# frankfurt_eth_arm.net
KiCad netlist of a schematic drawn in EAGLE
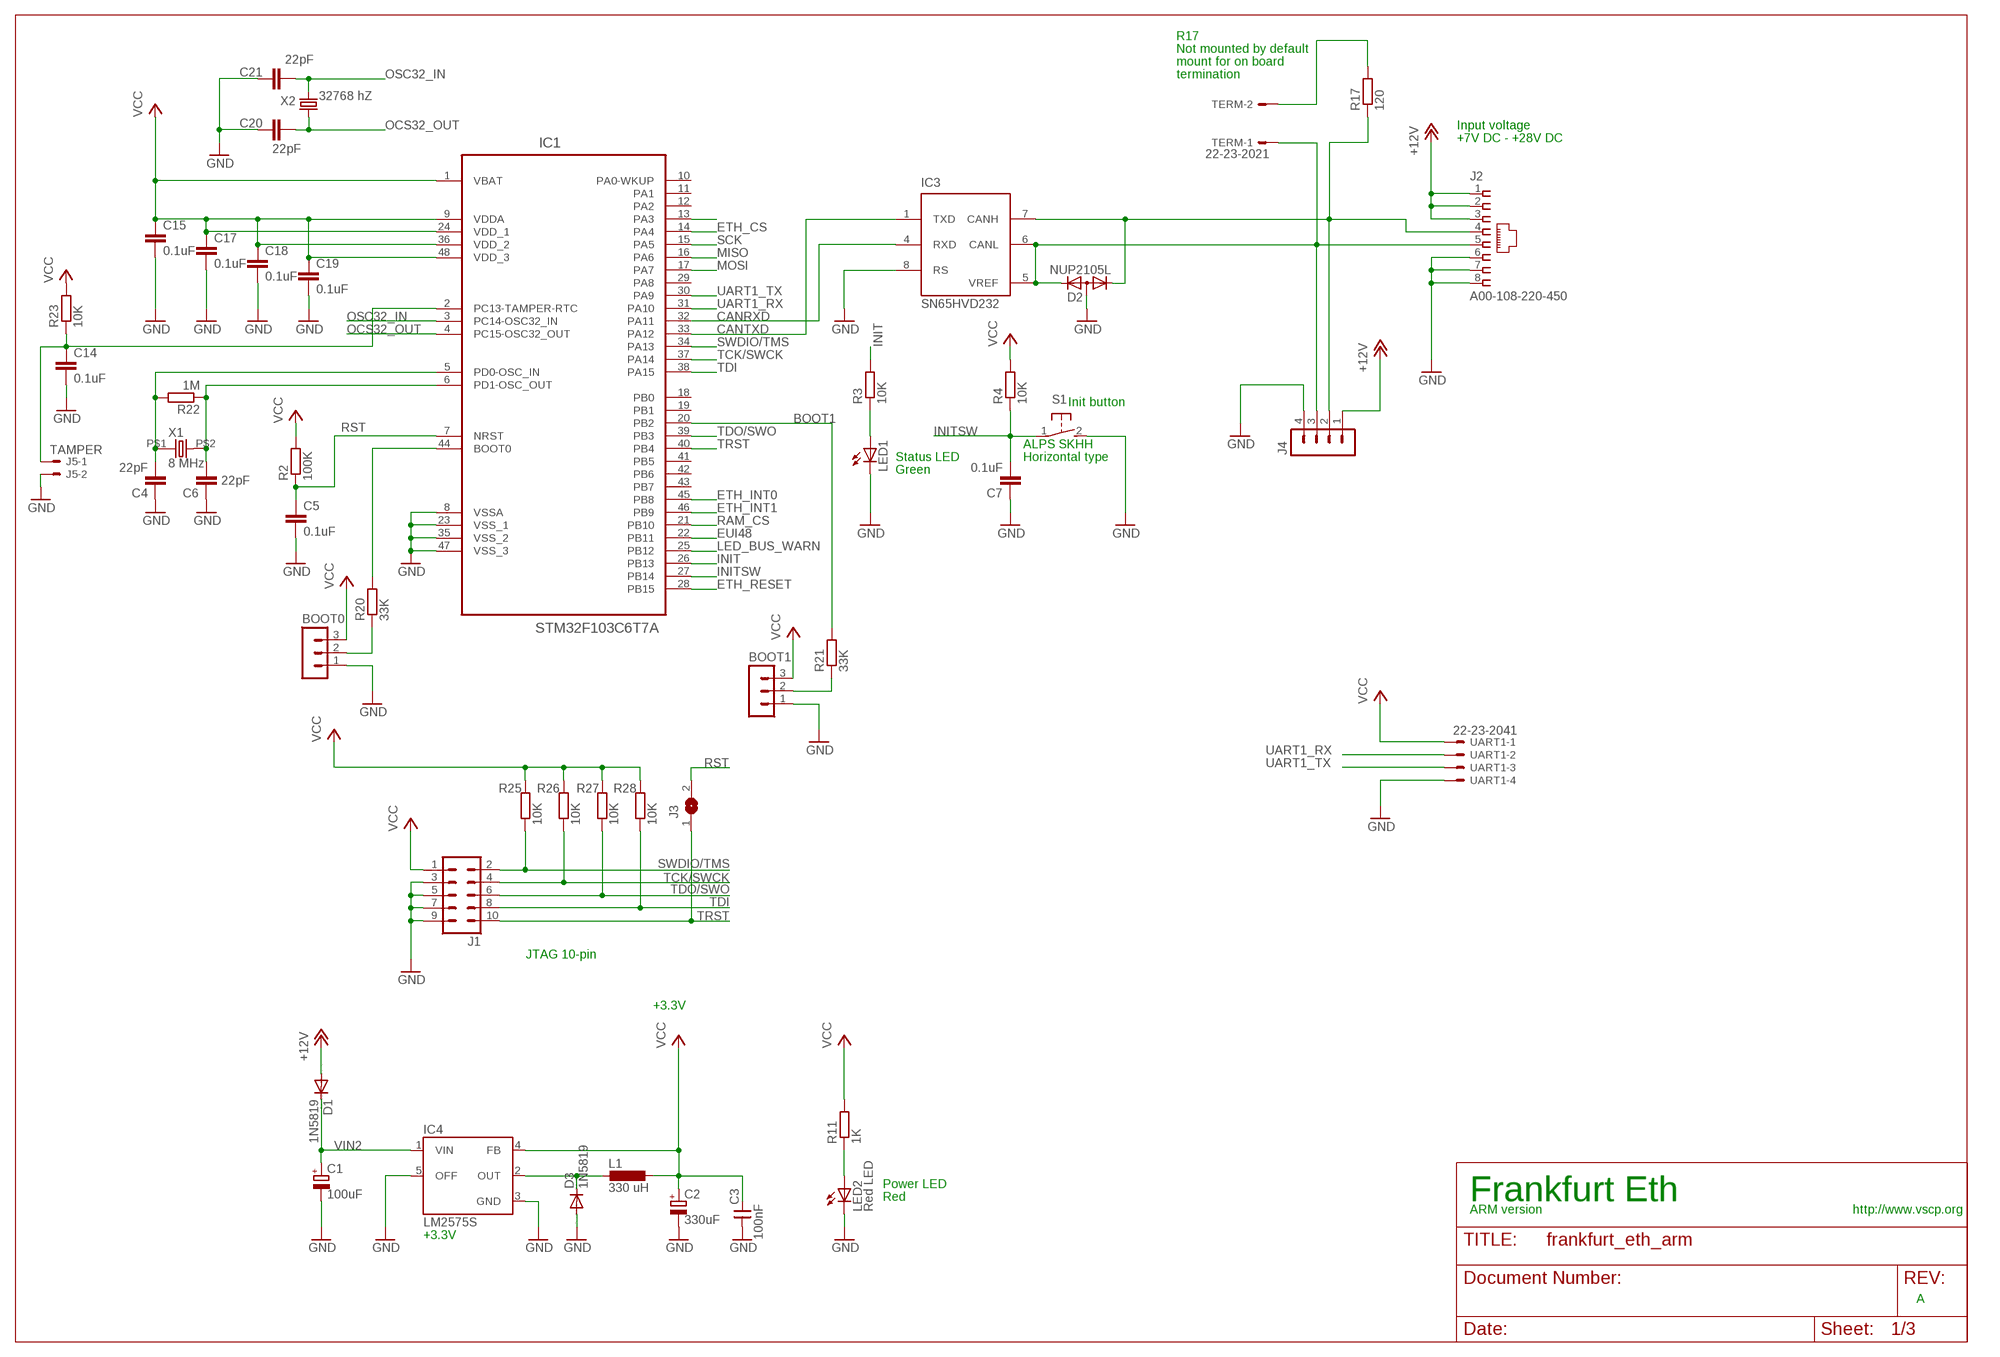
[diagram p0: schematic, sheet 1]
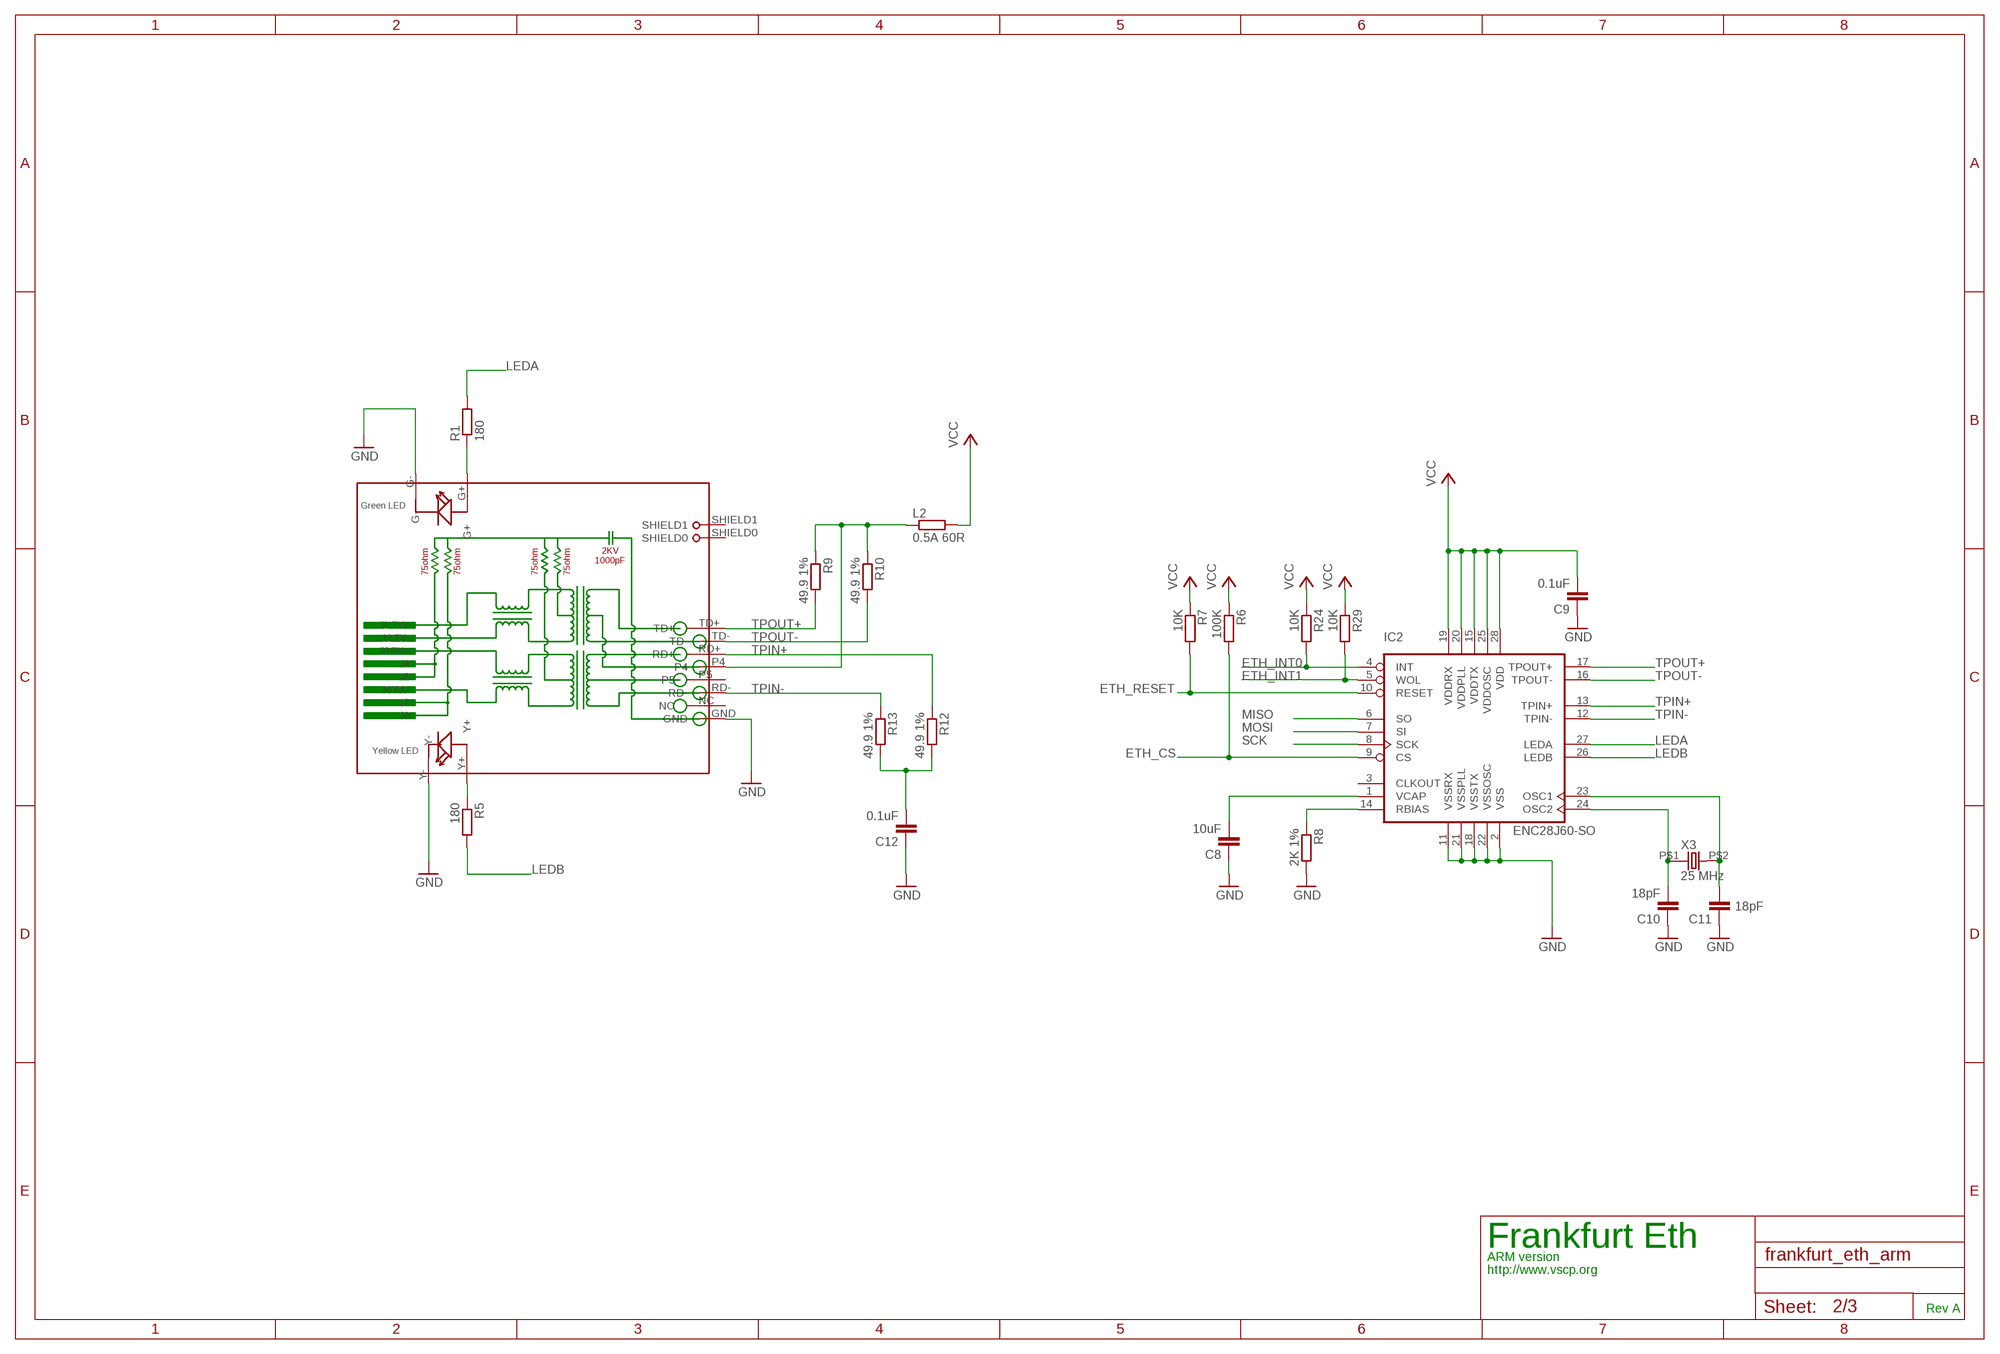
[diagram p1: schematic, sheet 2]
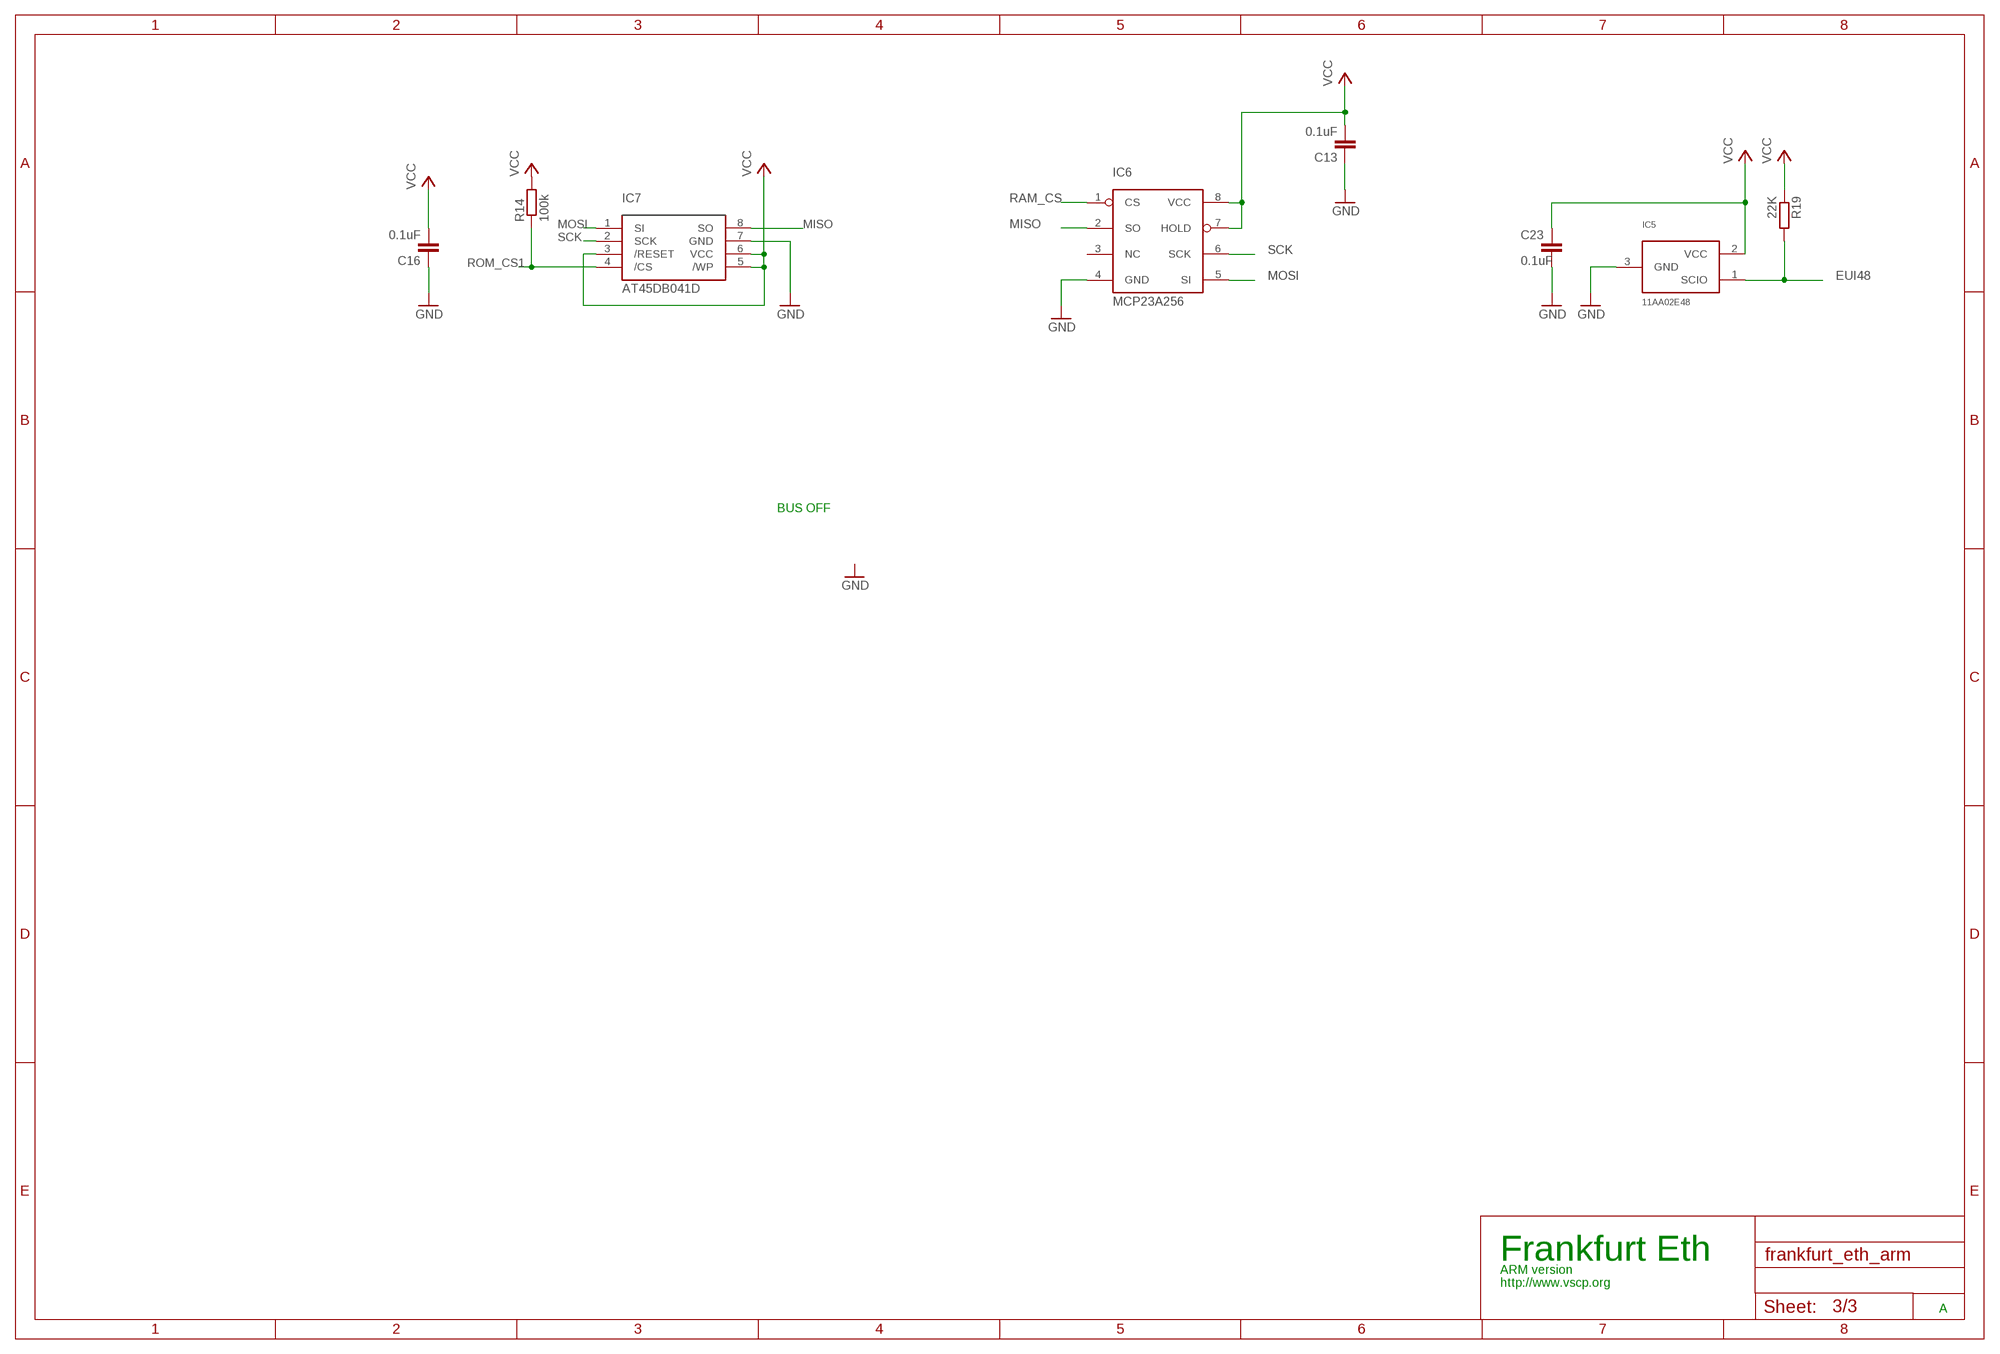
[diagram p2: schematic, sheet 3]

(export (version "E")
  (design (tool "Eeschema 10.0.6"))
  (components
    (comp (ref "BOOT0")
      (value "MA03-1")
      (footprint "eagle-import:MA03-1")
      (libsource (lib "eagle-import") (part "MA03-1"))
    )
    (comp (ref "BOOT1")
      (value "MA03-1")
      (footprint "eagle-import:MA03-1")
      (libsource (lib "eagle-import") (part "MA03-1"))
    )
    (comp (ref "C1")
      (value "100uF")
      (footprint "eagle-import:PANASONIC_D")
      (libsource (lib "eagle-import") (part "CPOL-EUD"))
    )
    (comp (ref "C2")
      (value "330uF")
      (footprint "eagle-import:PANASONIC_D")
      (libsource (lib "eagle-import") (part "CPOL-EUD"))
    )
    (comp (ref "C3")
      (value "100nF")
      (footprint "eagle-import:0805")
      (libsource (lib "eagle-import") (part "CNP-0805"))
    )
    (comp (ref "C4")
      (value "22pF")
      (footprint "eagle-import:C0805")
      (libsource (lib "eagle-import") (part "C-EUC0805"))
    )
    (comp (ref "C5")
      (value "0.1uF")
      (footprint "eagle-import:C0805")
      (libsource (lib "eagle-import") (part "C-EUC0805"))
    )
    (comp (ref "C6")
      (value "22pF")
      (footprint "eagle-import:C0805")
      (libsource (lib "eagle-import") (part "C-EUC0805"))
    )
    (comp (ref "C7")
      (value "0.1uF")
      (footprint "eagle-import:C0805")
      (libsource (lib "eagle-import") (part "C-EUC0805"))
    )
    (comp (ref "C14")
      (value "0.1uF")
      (footprint "eagle-import:C0805")
      (libsource (lib "eagle-import") (part "C-EUC0805"))
    )
    (comp (ref "C15")
      (value "0.1uF")
      (footprint "eagle-import:C0805")
      (libsource (lib "eagle-import") (part "C-EUC0805"))
    )
    (comp (ref "C17")
      (value "0.1uF")
      (footprint "eagle-import:C0805")
      (libsource (lib "eagle-import") (part "C-EUC0805"))
    )
    (comp (ref "C18")
      (value "0.1uF")
      (footprint "eagle-import:C0805")
      (libsource (lib "eagle-import") (part "C-EUC0805"))
    )
    (comp (ref "C19")
      (value "0.1uF")
      (footprint "eagle-import:C0805")
      (libsource (lib "eagle-import") (part "C-EUC0805"))
    )
    (comp (ref "C20")
      (value "22pF")
      (footprint "eagle-import:C0805")
      (libsource (lib "eagle-import") (part "C-EUC0805"))
    )
    (comp (ref "C21")
      (value "22pF")
      (footprint "eagle-import:C0805")
      (libsource (lib "eagle-import") (part "C-EUC0805"))
    )
    (comp (ref "D1")
      (value "1N5819")
      (footprint "eagle-import:SOD123")
      (libsource (lib "eagle-import") (part "DIODE-SOD123"))
    )
    (comp (ref "D2")
      (value "NUP2105L")
      (footprint "eagle-import:SOT23")
      (libsource (lib "eagle-import") (part "DIODE-2CA|ACSOT23"))
    )
    (comp (ref "D3")
      (value "1N5819")
      (footprint "eagle-import:SOD123")
      (libsource (lib "eagle-import") (part "DIODE-SOD123"))
    )
    (comp (ref "IC1")
      (value "STM32F103C6T7A")
      (footprint "eagle-import:QFP50P900X900X160-48N")
      (libsource (lib "eagle-import") (part "STM32F103C6T7A"))
    )
    (comp (ref "IC3")
      (value "SN65HVD232")
      (footprint "eagle-import:SO-08")
      (libsource (lib "eagle-import") (part "MCP2551SN"))
    )
    (comp (ref "IC4")
      (value "LM2575S")
      (footprint "eagle-import:TO263-5")
      (libsource (lib "eagle-import") (part "LM2575S"))
    )
    (comp (ref "J1")
      (value "MA05-2")
      (footprint "eagle-import:MA05-2")
      (libsource (lib "eagle-import") (part "MA05-2"))
    )
    (comp (ref "J2")
      (value "A00-108-220-450")
      (footprint "eagle-import:RJ-45")
      (libsource (lib "eagle-import") (part "A00-108-220-450"))
    )
    (comp (ref "J3") (value "SJ") (footprint "eagle-import:SJ") (libsource (lib "eagle-import") (part "SJ")))
    (comp (ref "J4")
      (value "MA04-1")
      (footprint "eagle-import:MA04-1")
      (libsource (lib "eagle-import") (part "MA04-1"))
    )
    (comp (ref "J5")
      (value "TAMPER")
      (footprint "eagle-import:22-23-2021")
      (fields (field (name "MF") "MOLEX") (field (name "MPN") "22-23-2021"))
      (libsource (lib "eagle-import") (part "22-23-2021"))
    )
    (comp (ref "L1")
      (value "330 uH")
      (footprint "eagle-import:DO3316P")
      (libsource (lib "eagle-import") (part "DO3316P"))
    )
    (comp (ref "LED1")
      (value "LEDCHIP-LED0805")
      (footprint "eagle-import:CHIP-LED0805")
      (libsource (lib "eagle-import") (part "LEDCHIP-LED0805"))
    )
    (comp (ref "LED2")
      (value "Red LED")
      (footprint "eagle-import:CHIP-LED0805")
      (libsource (lib "eagle-import") (part "LEDCHIP-LED0805"))
    )
    (comp (ref "R2")
      (value "100K")
      (footprint "eagle-import:R0805")
      (libsource (lib "eagle-import") (part "R-EU_R0805"))
    )
    (comp (ref "R3")
      (value "10K")
      (footprint "eagle-import:R0805")
      (libsource (lib "eagle-import") (part "R-EU_R0805"))
    )
    (comp (ref "R4")
      (value "10K")
      (footprint "eagle-import:R0805")
      (libsource (lib "eagle-import") (part "R-EU_R0805"))
    )
    (comp (ref "R11")
      (value "1K")
      (footprint "eagle-import:R0805")
      (libsource (lib "eagle-import") (part "R-EU_R0805"))
    )
    (comp (ref "R17")
      (value "120")
      (footprint "eagle-import:R0805")
      (libsource (lib "eagle-import") (part "R-EU_R0805"))
    )
    (comp (ref "R20")
      (value "33K")
      (footprint "eagle-import:R0805")
      (libsource (lib "eagle-import") (part "R-EU_R0805"))
    )
    (comp (ref "R21")
      (value "33K")
      (footprint "eagle-import:R0805")
      (libsource (lib "eagle-import") (part "R-EU_R0805"))
    )
    (comp (ref "R22")
      (value "1M")
      (footprint "eagle-import:R0805")
      (libsource (lib "eagle-import") (part "R-EU_R0805"))
    )
    (comp (ref "R23")
      (value "10K")
      (footprint "eagle-import:R0805")
      (libsource (lib "eagle-import") (part "R-EU_R0805"))
    )
    (comp (ref "R25")
      (value "10K")
      (footprint "eagle-import:R0805")
      (libsource (lib "eagle-import") (part "R-EU_R0805"))
    )
    (comp (ref "R26")
      (value "10K")
      (footprint "eagle-import:R0805")
      (libsource (lib "eagle-import") (part "R-EU_R0805"))
    )
    (comp (ref "R27")
      (value "10K")
      (footprint "eagle-import:R0805")
      (libsource (lib "eagle-import") (part "R-EU_R0805"))
    )
    (comp (ref "R28")
      (value "10K")
      (footprint "eagle-import:R0805")
      (libsource (lib "eagle-import") (part "R-EU_R0805"))
    )
    (comp (ref "S1")
      (value "31-XX")
      (footprint "eagle-import:B3F-31XX")
      (fields (field (name "MPN") "B3F-3100"))
      (libsource (lib "eagle-import") (part "31-XX"))
    )
    (comp (ref "TERM")
      (value "22-23-2021")
      (footprint "eagle-import:22-23-2021")
      (fields (field (name "MF") "MOLEX"))
      (libsource (lib "eagle-import") (part "22-23-2021"))
    )
    (comp (ref "UART1")
      (value "22-23-2041")
      (footprint "eagle-import:22-23-2041")
      (fields (field (name "MF") "MOLEX"))
      (libsource (lib "eagle-import") (part "22-23-2041"))
    )
    (comp (ref "X1")
      (value "8 MHz")
      (footprint "eagle-import:9C")
      (libsource (lib "eagle-import") (part "HC-49S"))
    )
    (comp (ref "X2")
      (value "32768 hZ")
      (footprint "eagle-import:TC26H")
      (libsource (lib "eagle-import") (part "CRYSTALTC26H"))
    )
    (comp (ref "C8")
      (value "10uF")
      (footprint "eagle-import:C0805")
      (libsource (lib "eagle-import") (part "C-EUC0805"))
    )
    (comp (ref "C9")
      (value "0.1uF")
      (footprint "eagle-import:C0805")
      (libsource (lib "eagle-import") (part "C-EUC0805"))
    )
    (comp (ref "C10")
      (value "18pF")
      (footprint "eagle-import:C0805")
      (libsource (lib "eagle-import") (part "C-EUC0805"))
    )
    (comp (ref "C11")
      (value "18pF")
      (footprint "eagle-import:C0805")
      (libsource (lib "eagle-import") (part "C-EUC0805"))
    )
    (comp (ref "C12")
      (value "0.1uF")
      (footprint "eagle-import:C0805")
      (libsource (lib "eagle-import") (part "C-EUC0805"))
    )
    (comp (ref "IC2")
      (value "ENC28J60-SO")
      (footprint "eagle-import:SO28W")
      (libsource (lib "eagle-import") (part "ENC28J60-SO"))
    )
    (comp (ref "L2")
      (value "0.5A 60R")
      (footprint "eagle-import:R0805")
      (libsource (lib "eagle-import") (part "R-EU_R0805"))
    )
    (comp (ref "R1")
      (value "180")
      (footprint "eagle-import:R0805")
      (libsource (lib "eagle-import") (part "R-EU_R0805"))
    )
    (comp (ref "R5")
      (value "180")
      (footprint "eagle-import:R0805")
      (libsource (lib "eagle-import") (part "R-EU_R0805"))
    )
    (comp (ref "R6")
      (value "100K")
      (footprint "eagle-import:R0805")
      (libsource (lib "eagle-import") (part "R-EU_R0805"))
    )
    (comp (ref "R7")
      (value "10K")
      (footprint "eagle-import:R0805")
      (libsource (lib "eagle-import") (part "R-EU_R0805"))
    )
    (comp (ref "R8")
      (value "2K 1%")
      (footprint "eagle-import:R0805")
      (libsource (lib "eagle-import") (part "R-EU_R0805"))
    )
    (comp (ref "R9")
      (value "49.9 1%")
      (footprint "eagle-import:R0805")
      (libsource (lib "eagle-import") (part "R-EU_R0805"))
    )
    (comp (ref "R10")
      (value "49.9 1%")
      (footprint "eagle-import:R0805")
      (libsource (lib "eagle-import") (part "R-EU_R0805"))
    )
    (comp (ref "R12")
      (value "49.9 1%")
      (footprint "eagle-import:R0805")
      (libsource (lib "eagle-import") (part "R-EU_R0805"))
    )
    (comp (ref "R13")
      (value "49.9 1%")
      (footprint "eagle-import:R0805")
      (libsource (lib "eagle-import") (part "R-EU_R0805"))
    )
    (comp (ref "R24")
      (value "10K")
      (footprint "eagle-import:R0805")
      (libsource (lib "eagle-import") (part "R-EU_R0805"))
    )
    (comp (ref "R29")
      (value "10K")
      (footprint "eagle-import:R0805")
      (libsource (lib "eagle-import") (part "R-EU_R0805"))
    )
    (comp (ref "RJ1")
      (value "HR911105A")
      (footprint "eagle-import:HR911105A")
      (libsource (lib "eagle-import") (part "HR911105A"))
    )
    (comp (ref "X3")
      (value "25 MHz")
      (footprint "eagle-import:9C")
      (libsource (lib "eagle-import") (part "HC-49S"))
    )
    (comp (ref "C13")
      (value "0.1uF")
      (footprint "eagle-import:C0805")
      (libsource (lib "eagle-import") (part "C-EUC0805"))
    )
    (comp (ref "C16")
      (value "0.1uF")
      (footprint "eagle-import:C0805")
      (libsource (lib "eagle-import") (part "C-EUC0805"))
    )
    (comp (ref "C23")
      (value "0.1uF")
      (footprint "eagle-import:C0805")
      (libsource (lib "eagle-import") (part "C-EUC0805"))
    )
    (comp (ref "IC5")
      (value "11AA02E48")
      (footprint "eagle-import:SOT23")
      (libsource (lib "eagle-import") (part "11AA02E48"))
    )
    (comp (ref "IC6")
      (value "MCP23A256")
      (footprint "eagle-import:SO-8")
      (libsource (lib "eagle-import") (part "MCP23A256"))
    )
    (comp (ref "IC7")
      (value "AT45DB041D")
      (footprint "eagle-import:SOP8W")
      (libsource (lib "eagle-import") (part "AT45DB011DSOP8W"))
    )
    (comp (ref "R14")
      (value "100k")
      (footprint "eagle-import:M0805")
      (libsource (lib "eagle-import") (part "R-EU_M0805"))
    )
    (comp (ref "R19")
      (value "22K")
      (footprint "eagle-import:M0805")
      (libsource (lib "eagle-import") (part "R-EU_M0805"))
    )
  )
  (nets
    (net (code "1") (name "+12V") (class "Default")
      (node (ref "D1") (pin "A") (pinfunction "A_A") (pintype "passive"))
      (node (ref "J2") (pin "1") (pinfunction "1_1") (pintype "passive"))
      (node (ref "J2") (pin "2") (pinfunction "2_2") (pintype "passive"))
      (node (ref "J2") (pin "3") (pinfunction "3_3") (pintype "passive"))
      (node (ref "J4") (pin "1") (pinfunction "1_1") (pintype "passive"))
    )
    (net (code "2") (name "BOOT1") (class "Default")
      (node (ref "IC1") (pin "20") (pinfunction "PB2_20") (pintype "bidirectional"))
      (node (ref "R21") (pin "2") (pinfunction "2_2") (pintype "passive"))
    )
    (net (code "3") (name "CANRXD") (class "Default")
      (node (ref "IC1") (pin "32") (pinfunction "PA11_32") (pintype "bidirectional"))
      (node (ref "IC3") (pin "4") (pinfunction "RXD_4") (pintype "output"))
    )
    (net (code "4") (name "CANTXD") (class "Default")
      (node (ref "IC1") (pin "33") (pinfunction "PA12_33") (pintype "bidirectional"))
      (node (ref "IC3") (pin "1") (pinfunction "TXD_1") (pintype "input"))
    )
    (net (code "5") (name "ETH_CS") (class "Default")
      (node (ref "IC1") (pin "14") (pinfunction "PA4_14") (pintype "bidirectional"))
      (node (ref "IC2") (pin "9") (pinfunction "CS_9") (pintype "input"))
      (node (ref "R6") (pin "2") (pinfunction "2_2") (pintype "passive"))
    )
    (net (code "6") (name "ETH_INT0") (class "Default")
      (node (ref "IC1") (pin "45") (pinfunction "PB8_45") (pintype "bidirectional"))
      (node (ref "IC2") (pin "4") (pinfunction "INT_4") (pintype "output"))
      (node (ref "R24") (pin "2") (pinfunction "2_2") (pintype "passive"))
    )
    (net (code "7") (name "ETH_INT1") (class "Default")
      (node (ref "IC1") (pin "46") (pinfunction "PB9_46") (pintype "bidirectional"))
      (node (ref "IC2") (pin "5") (pinfunction "WOL_5") (pintype "output"))
      (node (ref "R29") (pin "2") (pinfunction "2_2") (pintype "passive"))
    )
    (net (code "8") (name "ETH_RESET") (class "Default")
      (node (ref "IC1") (pin "28") (pinfunction "PB15_28") (pintype "bidirectional"))
      (node (ref "IC2") (pin "10") (pinfunction "RESET_10") (pintype "input"))
      (node (ref "R7") (pin "2") (pinfunction "2_2") (pintype "passive"))
    )
    (net (code "9") (name "EUI48") (class "Default")
      (node (ref "IC1") (pin "22") (pinfunction "PB11_22") (pintype "bidirectional"))
      (node (ref "IC5") (pin "1") (pinfunction "SCIO_1") (pintype "bidirectional"))
      (node (ref "R19") (pin "2") (pinfunction "2_2") (pintype "passive"))
    )
    (net (code "10") (name "GND") (class "Default")
      (node (ref "BOOT0") (pin "1") (pinfunction "1_1") (pintype "passive"))
      (node (ref "BOOT1") (pin "1") (pinfunction "1_1") (pintype "passive"))
      (node (ref "C1") (pin "-") (pinfunction "-_-") (pintype "passive"))
      (node (ref "C10") (pin "1") (pinfunction "1_1") (pintype "passive"))
      (node (ref "C11") (pin "1") (pinfunction "1_1") (pintype "passive"))
      (node (ref "C12") (pin "1") (pinfunction "1_1") (pintype "passive"))
      (node (ref "C13") (pin "1") (pinfunction "1_1") (pintype "passive"))
      (node (ref "C14") (pin "2") (pinfunction "2_2") (pintype "passive"))
      (node (ref "C15") (pin "2") (pinfunction "2_2") (pintype "passive"))
      (node (ref "C16") (pin "1") (pinfunction "1_1") (pintype "passive"))
      (node (ref "C17") (pin "2") (pinfunction "2_2") (pintype "passive"))
      (node (ref "C18") (pin "2") (pinfunction "2_2") (pintype "passive"))
      (node (ref "C19") (pin "2") (pinfunction "2_2") (pintype "passive"))
      (node (ref "C2") (pin "-") (pinfunction "-_-") (pintype "passive"))
      (node (ref "C20") (pin "1") (pinfunction "1_1") (pintype "passive"))
      (node (ref "C21") (pin "1") (pinfunction "1_1") (pintype "passive"))
      (node (ref "C23") (pin "2") (pinfunction "2_2") (pintype "passive"))
      (node (ref "C3") (pin "1") (pinfunction "1_1") (pintype "passive"))
      (node (ref "C4") (pin "1") (pinfunction "1_1") (pintype "passive"))
      (node (ref "C5") (pin "2") (pinfunction "2_2") (pintype "passive"))
      (node (ref "C6") (pin "1") (pinfunction "1_1") (pintype "passive"))
      (node (ref "C7") (pin "1") (pinfunction "1_1") (pintype "passive"))
      (node (ref "C8") (pin "1") (pinfunction "1_1") (pintype "passive"))
      (node (ref "C9") (pin "1") (pinfunction "1_1") (pintype "passive"))
      (node (ref "D2") (pin "3") (pinfunction "A_3") (pintype "passive"))
      (node (ref "D3") (pin "A") (pinfunction "A_A") (pintype "passive"))
      (node (ref "IC1") (pin "23") (pinfunction "VSS_1_23") (pintype "passive"))
      (node (ref "IC1") (pin "35") (pinfunction "VSS_2_35") (pintype "passive"))
      (node (ref "IC1") (pin "47") (pinfunction "VSS_3_47") (pintype "passive"))
      (node (ref "IC1") (pin "8") (pinfunction "VSSA_8") (pintype "passive"))
      (node (ref "IC2") (pin "11") (pinfunction "VSSRX_11") (pintype "power_in"))
      (node (ref "IC2") (pin "18") (pinfunction "VSSTX_18") (pintype "power_in"))
      (node (ref "IC2") (pin "2") (pinfunction "VSS_2") (pintype "power_in"))
      (node (ref "IC2") (pin "21") (pinfunction "VSSPLL_21") (pintype "power_in"))
      (node (ref "IC2") (pin "22") (pinfunction "VSSOSC_22") (pintype "power_in"))
      (node (ref "IC3") (pin "8") (pinfunction "RS_8") (pintype "input"))
      (node (ref "IC4") (pin "3") (pinfunction "GND_3") (pintype "power_in"))
      (node (ref "IC4") (pin "5") (pinfunction "OFF_5") (pintype "input"))
      (node (ref "IC5") (pin "3") (pinfunction "GND_3") (pintype "power_in"))
      (node (ref "IC6") (pin "4") (pinfunction "GND_4") (pintype "power_in"))
      (node (ref "IC7") (pin "7") (pinfunction "GND_7") (pintype "power_in"))
      (node (ref "J1") (pin "3") (pinfunction "3_3") (pintype "passive"))
      (node (ref "J1") (pin "5") (pinfunction "5_5") (pintype "passive"))
      (node (ref "J1") (pin "7") (pinfunction "7_7") (pintype "passive"))
      (node (ref "J1") (pin "9") (pinfunction "9_9") (pintype "passive"))
      (node (ref "J2") (pin "6") (pinfunction "6_6") (pintype "passive"))
      (node (ref "J2") (pin "7") (pinfunction "7_7") (pintype "passive"))
      (node (ref "J2") (pin "8") (pinfunction "8_8") (pintype "passive"))
      (node (ref "J4") (pin "4") (pinfunction "4_4") (pintype "passive"))
      (node (ref "J5") (pin "2") (pinfunction "S_2") (pintype "passive"))
      (node (ref "LED1") (pin "C") (pinfunction "C_C") (pintype "passive"))
      (node (ref "LED2") (pin "C") (pinfunction "C_C") (pintype "passive"))
      (node (ref "R8") (pin "2") (pinfunction "2_2") (pintype "passive"))
      (node (ref "RJ1") (pin "G-") (pinfunction "G-_G-") (pintype "bidirectional"))
      (node (ref "RJ1") (pin "GND") (pinfunction "GND_GND") (pintype "bidirectional"))
      (node (ref "RJ1") (pin "Y-") (pinfunction "Y-_Y-") (pintype "bidirectional"))
      (node (ref "S1") (pin "2") (pinfunction "S_2") (pintype "passive"))
      (node (ref "UART1") (pin "4") (pinfunction "S_4") (pintype "passive"))
    )
    (net (code "11") (name "INIT") (class "Default")
      (node (ref "IC1") (pin "26") (pinfunction "PB13_26") (pintype "bidirectional"))
      (node (ref "R3") (pin "2") (pinfunction "2_2") (pintype "passive"))
    )
    (net (code "12") (name "INITSW") (class "Default")
      (node (ref "C7") (pin "2") (pinfunction "2_2") (pintype "passive"))
      (node (ref "IC1") (pin "27") (pinfunction "PB14_27") (pintype "bidirectional"))
      (node (ref "R4") (pin "1") (pinfunction "1_1") (pintype "passive"))
      (node (ref "S1") (pin "1") (pinfunction "P_1") (pintype "passive"))
    )
    (net (code "13") (name "LEDA") (class "Default")
      (node (ref "IC2") (pin "27") (pinfunction "LEDA_27") (pintype "output"))
      (node (ref "R1") (pin "2") (pinfunction "2_2") (pintype "passive"))
    )
    (net (code "14") (name "LEDB") (class "Default")
      (node (ref "IC2") (pin "26") (pinfunction "LEDB_26") (pintype "output"))
      (node (ref "R5") (pin "2") (pinfunction "2_2") (pintype "passive"))
    )
    (net (code "15") (name "LED_BUS_WARN") (class "Default")
      (node (ref "IC1") (pin "25") (pinfunction "PB12_25") (pintype "bidirectional"))
    )
    (net (code "16") (name "MISO") (class "Default")
      (node (ref "IC1") (pin "16") (pinfunction "PA6_16") (pintype "bidirectional"))
      (node (ref "IC2") (pin "6") (pinfunction "SO_6") (pintype "output"))
      (node (ref "IC6") (pin "2") (pinfunction "SO_2") (pintype "output"))
      (node (ref "IC7") (pin "8") (pinfunction "SO_8") (pintype "output"))
    )
    (net (code "17") (name "MOSI") (class "Default")
      (node (ref "IC1") (pin "17") (pinfunction "PA7_17") (pintype "bidirectional"))
      (node (ref "IC2") (pin "7") (pinfunction "SI_7") (pintype "input"))
      (node (ref "IC6") (pin "5") (pinfunction "SI_5") (pintype "input"))
      (node (ref "IC7") (pin "1") (pinfunction "SI_1") (pintype "input"))
    )
    (net (code "18") (name "Net-(BOOT0-Pad2)") (class "Default")
      (node (ref "BOOT0") (pin "2") (pinfunction "2_2") (pintype "passive"))
      (node (ref "R20") (pin "1") (pinfunction "1_1") (pintype "passive"))
    )
    (net (code "19") (name "Net-(BOOT1-Pad2)") (class "Default")
      (node (ref "BOOT1") (pin "2") (pinfunction "2_2") (pintype "passive"))
      (node (ref "R21") (pin "1") (pinfunction "1_1") (pintype "passive"))
    )
    (net (code "20") (name "Net-(C12-Pad2)") (class "Default")
      (node (ref "C12") (pin "2") (pinfunction "2_2") (pintype "passive"))
      (node (ref "R12") (pin "2") (pinfunction "2_2") (pintype "passive"))
      (node (ref "R13") (pin "2") (pinfunction "2_2") (pintype "passive"))
    )
    (net (code "21") (name "Net-(D2-K1)") (class "Default")
      (node (ref "D2") (pin "1") (pinfunction "K1_1") (pintype "passive"))
      (node (ref "IC3") (pin "7") (pinfunction "CANH_7") (pintype "bidirectional"))
      (node (ref "J2") (pin "4") (pinfunction "4_4") (pintype "passive"))
      (node (ref "J4") (pin "2") (pinfunction "2_2") (pintype "passive"))
      (node (ref "R17") (pin "1") (pinfunction "1_1") (pintype "passive"))
    )
    (net (code "22") (name "Net-(D2-K2)") (class "Default")
      (node (ref "D2") (pin "2") (pinfunction "K2_2") (pintype "passive"))
      (node (ref "IC3") (pin "5") (pinfunction "VREF_5") (pintype "power_in"))
      (node (ref "IC3") (pin "6") (pinfunction "CANL_6") (pintype "bidirectional"))
      (node (ref "J2") (pin "5") (pinfunction "5_5") (pintype "passive"))
      (node (ref "J4") (pin "3") (pinfunction "3_3") (pintype "passive"))
      (node (ref "TERM") (pin "1") (pinfunction "S_1") (pintype "passive"))
    )
    (net (code "23") (name "Net-(IC1-BOOT0)") (class "Default")
      (node (ref "IC1") (pin "44") (pinfunction "BOOT0_44") (pintype "input"))
      (node (ref "R20") (pin "2") (pinfunction "2_2") (pintype "passive"))
    )
    (net (code "24") (name "Net-(IC1-PC13-TAMPER-RTC)") (class "Default")
      (node (ref "C14") (pin "1") (pinfunction "1_1") (pintype "passive"))
      (node (ref "IC1") (pin "2") (pinfunction "PC13-TAMPER-RTC_2") (pintype "bidirectional"))
      (node (ref "J5") (pin "1") (pinfunction "S_1") (pintype "passive"))
      (node (ref "R23") (pin "1") (pinfunction "1_1") (pintype "passive"))
    )
    (net (code "25") (name "Net-(IC1-PD0-OSC_IN)") (class "Default")
      (node (ref "C4") (pin "2") (pinfunction "2_2") (pintype "passive"))
      (node (ref "IC1") (pin "5") (pinfunction "PD0-OSC_IN_5") (pintype "bidirectional"))
      (node (ref "R22") (pin "2") (pinfunction "2_2") (pintype "passive"))
      (node (ref "X1") (pin "P$1") (pinfunction "1_P$1") (pintype "passive"))
    )
    (net (code "26") (name "Net-(IC1-PD1-OSC_OUT)") (class "Default")
      (node (ref "C6") (pin "2") (pinfunction "2_2") (pintype "passive"))
      (node (ref "IC1") (pin "6") (pinfunction "PD1-OSC_OUT_6") (pintype "bidirectional"))
      (node (ref "R22") (pin "1") (pinfunction "1_1") (pintype "passive"))
      (node (ref "X1") (pin "P$2") (pinfunction "2_P$2") (pintype "passive"))
    )
    (net (code "27") (name "Net-(IC2-OSC1)") (class "Default")
      (node (ref "C11") (pin "2") (pinfunction "2_2") (pintype "passive"))
      (node (ref "IC2") (pin "23") (pinfunction "OSC1_23") (pintype "input"))
      (node (ref "X3") (pin "P$2") (pinfunction "2_P$2") (pintype "passive"))
    )
    (net (code "28") (name "Net-(IC2-OSC2)") (class "Default")
      (node (ref "C10") (pin "2") (pinfunction "2_2") (pintype "passive"))
      (node (ref "IC2") (pin "24") (pinfunction "OSC2_24") (pintype "output"))
      (node (ref "X3") (pin "P$1") (pinfunction "1_P$1") (pintype "passive"))
    )
    (net (code "29") (name "Net-(IC2-RBIAS)") (class "Default")
      (node (ref "IC2") (pin "14") (pinfunction "RBIAS_14") (pintype "passive"))
      (node (ref "R8") (pin "1") (pinfunction "1_1") (pintype "passive"))
    )
    (net (code "30") (name "Net-(IC2-VCAP)") (class "Default")
      (node (ref "C8") (pin "2") (pinfunction "2_2") (pintype "passive"))
      (node (ref "IC2") (pin "1") (pinfunction "VCAP_1") (pintype "power_in"))
    )
    (net (code "31") (name "Net-(IC4-OUT)") (class "Default")
      (node (ref "D3") (pin "C") (pinfunction "C_C") (pintype "passive"))
      (node (ref "IC4") (pin "2") (pinfunction "OUT_2") (pintype "output"))
      (node (ref "L1") (pin "1") (pinfunction "1_1") (pintype "passive"))
    )
    (net (code "32") (name "Net-(L2-Pad1)") (class "Default")
      (node (ref "L2") (pin "1") (pinfunction "1_1") (pintype "passive"))
      (node (ref "R10") (pin "1") (pinfunction "1_1") (pintype "passive"))
      (node (ref "R9") (pin "1") (pinfunction "1_1") (pintype "passive"))
      (node (ref "RJ1") (pin "P4") (pinfunction "P4_P4") (pintype "bidirectional"))
    )
    (net (code "33") (name "Net-(LED1-PadA)") (class "Default")
      (node (ref "LED1") (pin "A") (pinfunction "A_A") (pintype "passive"))
      (node (ref "R3") (pin "1") (pinfunction "1_1") (pintype "passive"))
    )
    (net (code "34") (name "Net-(LED2-PadA)") (class "Default")
      (node (ref "LED2") (pin "A") (pinfunction "A_A") (pintype "passive"))
      (node (ref "R11") (pin "1") (pinfunction "1_1") (pintype "passive"))
    )
    (net (code "35") (name "Net-(R1-Pad1)") (class "Default")
      (node (ref "R1") (pin "1") (pinfunction "1_1") (pintype "passive"))
      (node (ref "RJ1") (pin "G+") (pinfunction "G+_G+") (pintype "bidirectional"))
    )
    (net (code "36") (name "Net-(R5-Pad1)") (class "Default")
      (node (ref "R5") (pin "1") (pinfunction "1_1") (pintype "passive"))
      (node (ref "RJ1") (pin "Y+") (pinfunction "Y+_Y+") (pintype "bidirectional"))
    )
    (net (code "37") (name "Net-(TERMB-S)") (class "Default")
      (node (ref "R17") (pin "2") (pinfunction "2_2") (pintype "passive"))
      (node (ref "TERM") (pin "2") (pinfunction "S_2") (pintype "passive"))
    )
    (net (code "38") (name "OCS32_OUT") (class "Default")
      (node (ref "C20") (pin "2") (pinfunction "2_2") (pintype "passive"))
      (node (ref "IC1") (pin "4") (pinfunction "PC15-OSC32_OUT_4") (pintype "bidirectional"))
      (node (ref "X2") (pin "1") (pinfunction "1_1") (pintype "passive"))
    )
    (net (code "39") (name "OSC32_IN") (class "Default")
      (node (ref "C21") (pin "2") (pinfunction "2_2") (pintype "passive"))
      (node (ref "IC1") (pin "3") (pinfunction "PC14-OSC32_IN_3") (pintype "bidirectional"))
      (node (ref "X2") (pin "2") (pinfunction "2_2") (pintype "passive"))
    )
    (net (code "40") (name "RAM_CS") (class "Default")
      (node (ref "IC1") (pin "21") (pinfunction "PB10_21") (pintype "bidirectional"))
      (node (ref "IC6") (pin "1") (pinfunction "CS_1") (pintype "input"))
    )
    (net (code "41") (name "ROM_CS1") (class "Default")
      (node (ref "IC1") (pin "13") (pinfunction "PA3_13") (pintype "bidirectional"))
      (node (ref "IC7") (pin "4") (pinfunction "/CS_4") (pintype "input"))
      (node (ref "R14") (pin "1") (pinfunction "1_1") (pintype "passive"))
    )
    (net (code "42") (name "RST") (class "Default")
      (node (ref "C5") (pin "1") (pinfunction "1_1") (pintype "passive"))
      (node (ref "IC1") (pin "7") (pinfunction "NRST_7") (pintype "bidirectional"))
      (node (ref "J3") (pin "2") (pinfunction "2_2") (pintype "passive"))
      (node (ref "R2") (pin "1") (pinfunction "1_1") (pintype "passive"))
    )
    (net (code "43") (name "SCK") (class "Default")
      (node (ref "IC1") (pin "15") (pinfunction "PA5_15") (pintype "bidirectional"))
      (node (ref "IC2") (pin "8") (pinfunction "SCK_8") (pintype "input"))
      (node (ref "IC6") (pin "6") (pinfunction "SCK_6") (pintype "input"))
      (node (ref "IC7") (pin "2") (pinfunction "SCK_2") (pintype "input"))
    )
    (net (code "44") (name "SWDIO{slash}TMS") (class "Default")
      (node (ref "IC1") (pin "34") (pinfunction "PA13_34") (pintype "bidirectional"))
      (node (ref "J1") (pin "2") (pinfunction "2_2") (pintype "passive"))
      (node (ref "R25") (pin "1") (pinfunction "1_1") (pintype "passive"))
    )
    (net (code "45") (name "TCK{slash}SWCK") (class "Default")
      (node (ref "IC1") (pin "37") (pinfunction "PA14_37") (pintype "bidirectional"))
      (node (ref "J1") (pin "4") (pinfunction "4_4") (pintype "passive"))
      (node (ref "R26") (pin "1") (pinfunction "1_1") (pintype "passive"))
    )
    (net (code "46") (name "TDI") (class "Default")
      (node (ref "IC1") (pin "38") (pinfunction "PA15_38") (pintype "bidirectional"))
      (node (ref "J1") (pin "8") (pinfunction "8_8") (pintype "passive"))
      (node (ref "R28") (pin "1") (pinfunction "1_1") (pintype "passive"))
    )
    (net (code "47") (name "TDO{slash}SWO") (class "Default")
      (node (ref "IC1") (pin "39") (pinfunction "PB3_39") (pintype "bidirectional"))
      (node (ref "J1") (pin "6") (pinfunction "6_6") (pintype "passive"))
      (node (ref "R27") (pin "1") (pinfunction "1_1") (pintype "passive"))
    )
    (net (code "48") (name "TPIN+") (class "Default")
      (node (ref "IC2") (pin "13") (pinfunction "TPIN+_13") (pintype "input"))
      (node (ref "R12") (pin "1") (pinfunction "1_1") (pintype "passive"))
      (node (ref "RJ1") (pin "RD+") (pinfunction "RD+_RD+") (pintype "bidirectional"))
    )
    (net (code "49") (name "TPIN-") (class "Default")
      (node (ref "IC2") (pin "12") (pinfunction "TPIN-_12") (pintype "input"))
      (node (ref "R13") (pin "1") (pinfunction "1_1") (pintype "passive"))
      (node (ref "RJ1") (pin "RD-") (pinfunction "RD-_RD-") (pintype "bidirectional"))
    )
    (net (code "50") (name "TPOUT+") (class "Default")
      (node (ref "IC2") (pin "17") (pinfunction "TPOUT+_17") (pintype "output"))
      (node (ref "R9") (pin "2") (pinfunction "2_2") (pintype "passive"))
      (node (ref "RJ1") (pin "TD+") (pinfunction "TD+_TD+") (pintype "bidirectional"))
    )
    (net (code "51") (name "TPOUT-") (class "Default")
      (node (ref "IC2") (pin "16") (pinfunction "TPOUT-_16") (pintype "output"))
      (node (ref "R10") (pin "2") (pinfunction "2_2") (pintype "passive"))
      (node (ref "RJ1") (pin "TD-") (pinfunction "TD-_TD-") (pintype "bidirectional"))
    )
    (net (code "52") (name "TRST") (class "Default")
      (node (ref "IC1") (pin "40") (pinfunction "PB4_40") (pintype "bidirectional"))
      (node (ref "J1") (pin "10") (pinfunction "10_10") (pintype "passive"))
      (node (ref "J3") (pin "1") (pinfunction "1_1") (pintype "passive"))
    )
    (net (code "53") (name "UART1_RX") (class "Default")
      (node (ref "IC1") (pin "31") (pinfunction "PA10_31") (pintype "bidirectional"))
      (node (ref "UART1") (pin "2") (pinfunction "S_2") (pintype "passive"))
    )
    (net (code "54") (name "UART1_TX") (class "Default")
      (node (ref "IC1") (pin "30") (pinfunction "PA9_30") (pintype "bidirectional"))
      (node (ref "UART1") (pin "3") (pinfunction "S_3") (pintype "passive"))
    )
    (net (code "55") (name "VCC") (class "Default")
      (node (ref "BOOT0") (pin "3") (pinfunction "3_3") (pintype "passive"))
      (node (ref "BOOT1") (pin "3") (pinfunction "3_3") (pintype "passive"))
      (node (ref "C13") (pin "2") (pinfunction "2_2") (pintype "passive"))
      (node (ref "C15") (pin "1") (pinfunction "1_1") (pintype "passive"))
      (node (ref "C16") (pin "2") (pinfunction "2_2") (pintype "passive"))
      (node (ref "C17") (pin "1") (pinfunction "1_1") (pintype "passive"))
      (node (ref "C18") (pin "1") (pinfunction "1_1") (pintype "passive"))
      (node (ref "C19") (pin "1") (pinfunction "1_1") (pintype "passive"))
      (node (ref "C2") (pin "+") (pinfunction "+_+") (pintype "passive"))
      (node (ref "C23") (pin "1") (pinfunction "1_1") (pintype "passive"))
      (node (ref "C3") (pin "2") (pinfunction "2_2") (pintype "passive"))
      (node (ref "C9") (pin "2") (pinfunction "2_2") (pintype "passive"))
      (node (ref "IC1") (pin "1") (pinfunction "VBAT_1") (pintype "power_in"))
      (node (ref "IC1") (pin "24") (pinfunction "VDD_1_24") (pintype "power_in"))
      (node (ref "IC1") (pin "36") (pinfunction "VDD_2_36") (pintype "power_in"))
      (node (ref "IC1") (pin "48") (pinfunction "VDD_3_48") (pintype "power_in"))
      (node (ref "IC1") (pin "9") (pinfunction "VDDA_9") (pintype "power_in"))
      (node (ref "IC2") (pin "15") (pinfunction "VDDTX_15") (pintype "power_in"))
      (node (ref "IC2") (pin "19") (pinfunction "VDDRX_19") (pintype "power_in"))
      (node (ref "IC2") (pin "20") (pinfunction "VDDPLL_20") (pintype "power_in"))
      (node (ref "IC2") (pin "25") (pinfunction "VDDOSC_25") (pintype "power_in"))
      (node (ref "IC2") (pin "28") (pinfunction "VDD_28") (pintype "power_in"))
      (node (ref "IC4") (pin "4") (pinfunction "FB_4") (pintype "input"))
      (node (ref "IC5") (pin "2") (pinfunction "VCC_2") (pintype "power_in"))
      (node (ref "IC6") (pin "7") (pinfunction "HOLD_7") (pintype "input"))
      (node (ref "IC6") (pin "8") (pinfunction "VCC_8") (pintype "power_in"))
      (node (ref "IC7") (pin "3") (pinfunction "/RESET_3") (pintype "input"))
      (node (ref "IC7") (pin "5") (pinfunction "/WP_5") (pintype "input"))
      (node (ref "IC7") (pin "6") (pinfunction "VCC_6") (pintype "power_in"))
      (node (ref "J1") (pin "1") (pinfunction "1_1") (pintype "passive"))
      (node (ref "L1") (pin "2") (pinfunction "2_2") (pintype "passive"))
      (node (ref "L2") (pin "2") (pinfunction "2_2") (pintype "passive"))
      (node (ref "R11") (pin "2") (pinfunction "2_2") (pintype "passive"))
      (node (ref "R14") (pin "2") (pinfunction "2_2") (pintype "passive"))
      (node (ref "R19") (pin "1") (pinfunction "1_1") (pintype "passive"))
      (node (ref "R2") (pin "2") (pinfunction "2_2") (pintype "passive"))
      (node (ref "R23") (pin "2") (pinfunction "2_2") (pintype "passive"))
      (node (ref "R24") (pin "1") (pinfunction "1_1") (pintype "passive"))
      (node (ref "R25") (pin "2") (pinfunction "2_2") (pintype "passive"))
      (node (ref "R26") (pin "2") (pinfunction "2_2") (pintype "passive"))
      (node (ref "R27") (pin "2") (pinfunction "2_2") (pintype "passive"))
      (node (ref "R28") (pin "2") (pinfunction "2_2") (pintype "passive"))
      (node (ref "R29") (pin "1") (pinfunction "1_1") (pintype "passive"))
      (node (ref "R4") (pin "2") (pinfunction "2_2") (pintype "passive"))
      (node (ref "R6") (pin "1") (pinfunction "1_1") (pintype "passive"))
      (node (ref "R7") (pin "1") (pinfunction "1_1") (pintype "passive"))
      (node (ref "UART1") (pin "1") (pinfunction "S_1") (pintype "passive"))
    )
    (net (code "56") (name "VIN2") (class "Default")
      (node (ref "C1") (pin "+") (pinfunction "+_+") (pintype "passive"))
      (node (ref "D1") (pin "C") (pinfunction "C_C") (pintype "passive"))
      (node (ref "IC4") (pin "1") (pinfunction "VIN_1") (pintype "power_in"))
    )
    (net (code "57") (name "unconnected-(IC1-PA0-WKUP-Pad10)") (class "Default")
      (node (ref "IC1") (pin "10") (pinfunction "PA0-WKUP_10") (pintype "bidirectional"))
    )
    (net (code "58") (name "unconnected-(IC1-PA1-Pad11)") (class "Default")
      (node (ref "IC1") (pin "11") (pinfunction "PA1_11") (pintype "bidirectional"))
    )
    (net (code "59") (name "unconnected-(IC1-PA2-Pad12)") (class "Default")
      (node (ref "IC1") (pin "12") (pinfunction "PA2_12") (pintype "bidirectional"))
    )
    (net (code "60") (name "unconnected-(IC1-PA8-Pad29)") (class "Default")
      (node (ref "IC1") (pin "29") (pinfunction "PA8_29") (pintype "bidirectional"))
    )
    (net (code "61") (name "unconnected-(IC1-PB0-Pad18)") (class "Default")
      (node (ref "IC1") (pin "18") (pinfunction "PB0_18") (pintype "bidirectional"))
    )
    (net (code "62") (name "unconnected-(IC1-PB1-Pad19)") (class "Default")
      (node (ref "IC1") (pin "19") (pinfunction "PB1_19") (pintype "bidirectional"))
    )
    (net (code "63") (name "unconnected-(IC1-PB5-Pad41)") (class "Default")
      (node (ref "IC1") (pin "41") (pinfunction "PB5_41") (pintype "bidirectional"))
    )
    (net (code "64") (name "unconnected-(IC1-PB6-Pad42)") (class "Default")
      (node (ref "IC1") (pin "42") (pinfunction "PB6_42") (pintype "bidirectional"))
    )
    (net (code "65") (name "unconnected-(IC1-PB7-Pad43)") (class "Default")
      (node (ref "IC1") (pin "43") (pinfunction "PB7_43") (pintype "bidirectional"))
    )
    (net (code "66") (name "unconnected-(IC2-CLKOUT-Pad3)") (class "Default")
      (node (ref "IC2") (pin "3") (pinfunction "CLKOUT_3") (pintype "output"))
    )
    (net (code "67") (name "unconnected-(IC6-NC-Pad3)") (class "Default")
      (node (ref "IC6") (pin "3") (pinfunction "NC_3") (pintype "no_connect"))
    )
    (net (code "68") (name "unconnected-(RJ1-PadNC)") (class "Default")
      (node (ref "RJ1") (pin "NC") (pinfunction "NC_NC") (pintype "bidirectional"))
    )
    (net (code "69") (name "unconnected-(RJ1-PadP5)") (class "Default")
      (node (ref "RJ1") (pin "P5") (pinfunction "P5_P5") (pintype "bidirectional"))
    )
    (net (code "70") (name "unconnected-(RJ1-PadSHIELD0)") (class "Default")
      (node (ref "RJ1") (pin "SHIELD0") (pinfunction "SHIELD0_SHIELD0") (pintype "bidirectional"))
    )
    (net (code "71") (name "unconnected-(RJ1-PadSHIELD1)") (class "Default")
      (node (ref "RJ1") (pin "SHIELD1") (pinfunction "SHIELD1_SHIELD1") (pintype "bidirectional"))
    )
  )
)
